# Sheet1.net
KiCad netlist of a schematic drawn in Altium Designer
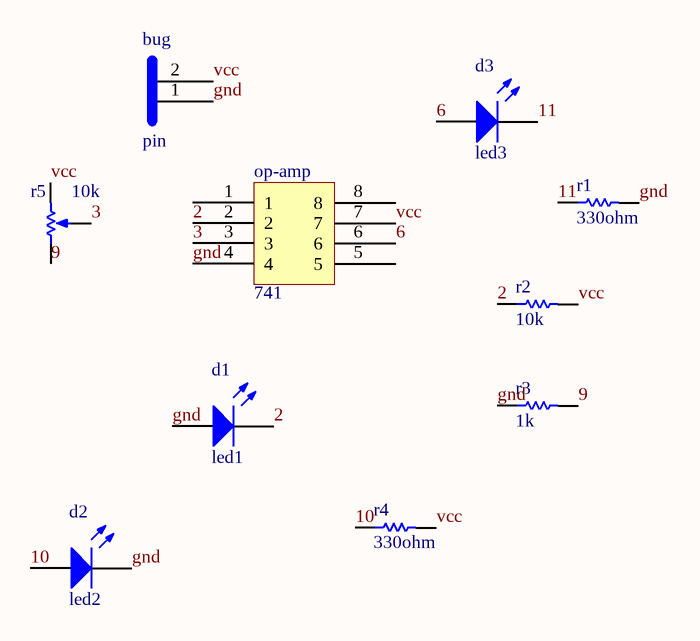
[diagram p0: Sheet1.SchDoc]

(export (version "E")
  (design (tool "Eeschema 10.0.6"))
  (components
    (comp (ref "bug")
      (value "pin")
      (footprint "bergstrip-2pin")
      (libsource (lib "Devindia_v2.0") (part "BURG STRIP 2"))
    )
    (comp (ref "d1")
      (value "led1")
      (footprint "LED-BLUE")
      (description "Typical BLUE SiC LED")
      (fields (field (name "PUBLISHER") "Altium Limited"))
      (libsource (lib "Devindia_v2.0") (part "LED-BLUE"))
    )
    (comp (ref "d2")
      (value "led2")
      (footprint "LED-BLUE")
      (description "Typical BLUE SiC LED")
      (fields (field (name "PUBLISHER") "Altium Limited"))
      (libsource (lib "Devindia_v2.0") (part "LED-BLUE"))
    )
    (comp (ref "d3")
      (value "led3")
      (footprint "LED-BLUE")
      (description "Typical BLUE SiC LED")
      (fields (field (name "PUBLISHER") "Altium Limited"))
      (libsource (lib "Devindia_v2.0") (part "LED-BLUE"))
    )
    (comp (ref "op-amp")
      (value "741")
      (footprint "dip-8pin")
      (libsource (lib "Devindia_v2.0") (part "dip-8pin"))
    )
    (comp (ref "r1")
      (value "330ohm")
      (footprint "res-2.54x4")
      (libsource (lib "Devindia_v2.0") (part "Resistor 2.54x4"))
    )
    (comp (ref "r2")
      (value "10k")
      (footprint "res-2.54x4")
      (libsource (lib "Devindia_v2.0") (part "Resistor 2.54x4"))
    )
    (comp (ref "r3")
      (value "1k")
      (footprint "res-2.54x4")
      (libsource (lib "Devindia_v2.0") (part "Resistor 2.54x4"))
    )
    (comp (ref "r4")
      (value "330ohm")
      (footprint "res-2.54x4")
      (libsource (lib "Devindia_v2.0") (part "Resistor 2.54x4"))
    )
    (comp (ref "r5")
      (value "10k")
      (footprint "reg-variable")
      (libsource (lib "Devindia_v2.0") (part "Variable Resistor"))
    )
  )
  (nets
    (net (code "1") (name "/2") (class "Default")
      (node (ref "d1") (pin "2") (pinfunction "K_2") (pintype "passive"))
      (node (ref "op-amp") (pin "2") (pinfunction "2_2") (pintype "passive"))
      (node (ref "r2") (pin "1") (pinfunction "1_1") (pintype "passive"))
    )
    (net (code "2") (name "/3") (class "Default")
      (node (ref "op-amp") (pin "3") (pinfunction "3_3") (pintype "passive"))
      (node (ref "r5") (pin "3") (pinfunction "TAP_3") (pintype "passive"))
    )
    (net (code "3") (name "/6") (class "Default")
      (node (ref "d3") (pin "1") (pinfunction "A_1") (pintype "passive"))
      (node (ref "op-amp") (pin "6") (pinfunction "6_6") (pintype "passive"))
    )
    (net (code "4") (name "/9") (class "Default")
      (node (ref "r3") (pin "2") (pinfunction "2_2") (pintype "passive"))
      (node (ref "r5") (pin "1") (pinfunction "TOP_1") (pintype "passive"))
    )
    (net (code "5") (name "/10") (class "Default")
      (node (ref "d2") (pin "1") (pinfunction "A_1") (pintype "passive"))
      (node (ref "r4") (pin "1") (pinfunction "1_1") (pintype "passive"))
    )
    (net (code "6") (name "/11") (class "Default")
      (node (ref "d3") (pin "2") (pinfunction "K_2") (pintype "passive"))
      (node (ref "r1") (pin "1") (pinfunction "1_1") (pintype "passive"))
    )
    (net (code "7") (name "/gnd") (class "Default")
      (node (ref "bug") (pin "1") (pinfunction "1_1") (pintype "passive"))
      (node (ref "d1") (pin "1") (pinfunction "A_1") (pintype "passive"))
      (node (ref "d2") (pin "2") (pinfunction "K_2") (pintype "passive"))
      (node (ref "op-amp") (pin "4") (pinfunction "4_4") (pintype "passive"))
      (node (ref "r1") (pin "2") (pinfunction "2_2") (pintype "passive"))
      (node (ref "r3") (pin "1") (pinfunction "1_1") (pintype "passive"))
    )
    (net (code "8") (name "/vcc") (class "Default")
      (node (ref "bug") (pin "2") (pinfunction "2_2") (pintype "passive"))
      (node (ref "op-amp") (pin "7") (pinfunction "7_7") (pintype "passive"))
      (node (ref "r2") (pin "2") (pinfunction "2_2") (pintype "passive"))
      (node (ref "r4") (pin "2") (pinfunction "2_2") (pintype "passive"))
      (node (ref "r5") (pin "2") (pinfunction "BOT_2") (pintype "passive"))
    )
    (net (code "9") (name "unconnected-(op-amp-Pad1)") (class "Default")
      (node (ref "op-amp") (pin "1") (pinfunction "1_1") (pintype "passive"))
    )
    (net (code "10") (name "unconnected-(op-amp-Pad5)") (class "Default")
      (node (ref "op-amp") (pin "5") (pinfunction "5_5") (pintype "passive"))
    )
    (net (code "11") (name "unconnected-(op-amp-Pad8)") (class "Default")
      (node (ref "op-amp") (pin "8") (pinfunction "8_8") (pintype "passive"))
    )
  )
)
